# Sheet2.net
KiCad netlist of a schematic drawn in Altium Designer
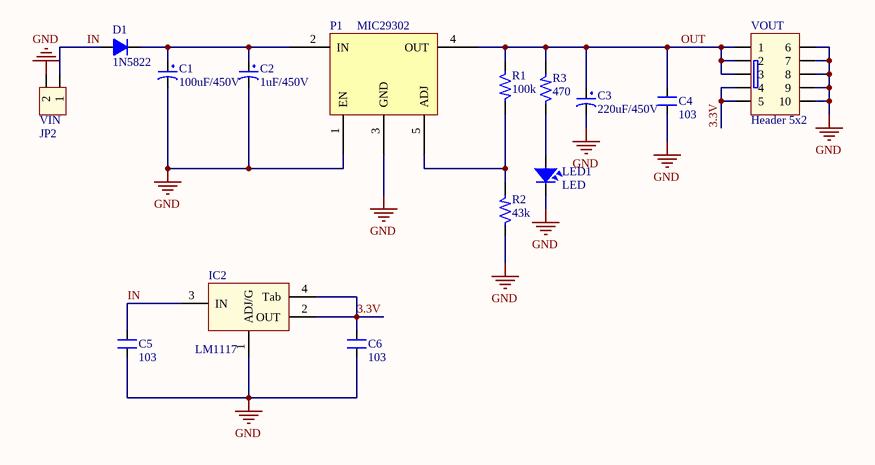
[diagram p0: Sheet2.SchDoc]

(export (version "E")
  (design (tool "Eeschema 10.0.6"))
  (components
    (comp (ref "C1")
      (value "100uF/450V")
      (footprint "CAP-D8-220uF/16V")
      (description "Cap 10000uF/63V")
      (libsource (lib "syhaunguyen") (part "CP9"))
    )
    (comp (ref "C2")
      (value "1uF/450V")
      (footprint "CAP0805")
      (description "Cap 10000uF/63V")
      (libsource (lib "syhaunguyen") (part "CP9"))
    )
    (comp (ref "C3")
      (value "220uF/450V")
      (footprint "CAP-D8-220uF/16V")
      (description "Cap 10000uF/63V")
      (libsource (lib "syhaunguyen") (part "CP9"))
    )
    (comp (ref "C4")
      (value "103")
      (footprint "SM-0805")
      (description "Cap SMD")
      (libsource (lib "syhaunguyen") (part "CM"))
    )
    (comp (ref "C5")
      (value "103")
      (footprint "SM-0805")
      (description "Cap SMD")
      (libsource (lib "syhaunguyen") (part "CM"))
    )
    (comp (ref "C6")
      (value "103")
      (footprint "SM-0805")
      (description "Cap SMD")
      (libsource (lib "syhaunguyen") (part "CM"))
    )
    (comp (ref "D1")
      (value "1N5822")
      (footprint "Diode1206")
      (description "Diode 5A")
      (libsource (lib "syhaunguyen") (part "D5A"))
    )
    (comp (ref "IC2")
      (value "LM1117")
      (footprint "SOT223-4N")
      (description "3v3")
      (libsource (lib "syhaunguyen") (part "LM1117"))
    )
    (comp (ref "LED1")
      (value "LED")
      (footprint "LED-5-RED")
      (description "LED Single colour Green and Red")
      (libsource (lib "syhaunguyen") (part "LED"))
    )
    (comp (ref "P1")
      (value "MIC29302")
      (footprint "LM2576_TO-263")
      (libsource (lib "Schlib1") (part "LM2576"))
    )
    (comp (ref "R1")
      (value "100k")
      (footprint "RES0805")
      (description "Resistor 1/4W")
      (libsource (lib "syhaunguyen") (part "R"))
    )
    (comp (ref "R2")
      (value "43k")
      (footprint "RES0805")
      (description "Resistor 1/4W")
      (libsource (lib "syhaunguyen") (part "R"))
    )
    (comp (ref "R3")
      (value "470")
      (footprint "RES0805")
      (description "Resistor 1/4W")
      (libsource (lib "syhaunguyen") (part "R"))
    )
    (comp (ref "VIN")
      (value "JP2")
      (footprint "DC-IN")
      (description "Connector 2")
      (libsource (lib "syhaunguyen") (part "Con2"))
    )
    (comp (ref "VOUT")
      (value "Header 5x2")
      (footprint "HED2X5_cen")
      (libsource (lib "syhaunguyen") (part "HED5x2"))
    )
  )
  (nets
    (net (code "1") (name "/3.3V") (class "Default")
      (node (ref "C6") (pin "2") (pinfunction "2_2") (pintype "passive"))
      (node (ref "IC2") (pin "2") (pinfunction "OUT_2") (pintype "passive"))
      (node (ref "IC2") (pin "4") (pinfunction "Tab_4") (pintype "passive"))
      (node (ref "VOUT") (pin "4") (pinfunction "4_4") (pintype "passive"))
      (node (ref "VOUT") (pin "5") (pinfunction "5_5") (pintype "passive"))
    )
    (net (code "2") (name "/IN") (class "Default")
      (node (ref "C5") (pin "2") (pinfunction "2_2") (pintype "passive"))
      (node (ref "D1") (pin "1") (pinfunction "A_1") (pintype "passive"))
      (node (ref "IC2") (pin "3") (pinfunction "IN_3") (pintype "passive"))
      (node (ref "VIN") (pin "1") (pinfunction "1_1") (pintype "passive"))
    )
    (net (code "3") (name "/OUT") (class "Default")
      (node (ref "C3") (pin "1") (pinfunction "1_1") (pintype "passive"))
      (node (ref "C4") (pin "2") (pinfunction "2_2") (pintype "passive"))
      (node (ref "P1") (pin "4") (pinfunction "OUT_4") (pintype "passive"))
      (node (ref "R1") (pin "1") (pinfunction "1_1") (pintype "passive"))
      (node (ref "R3") (pin "2") (pinfunction "2_2") (pintype "passive"))
      (node (ref "VOUT") (pin "1") (pinfunction "1_1") (pintype "passive"))
      (node (ref "VOUT") (pin "2") (pinfunction "2_2") (pintype "passive"))
      (node (ref "VOUT") (pin "3") (pinfunction "3_3") (pintype "passive"))
    )
    (net (code "4") (name "GND") (class "Default")
      (node (ref "C1") (pin "2") (pinfunction "2_2") (pintype "passive"))
      (node (ref "C2") (pin "2") (pinfunction "2_2") (pintype "passive"))
      (node (ref "C3") (pin "2") (pinfunction "2_2") (pintype "passive"))
      (node (ref "C4") (pin "1") (pinfunction "1_1") (pintype "passive"))
      (node (ref "C5") (pin "1") (pinfunction "1_1") (pintype "passive"))
      (node (ref "C6") (pin "1") (pinfunction "1_1") (pintype "passive"))
      (node (ref "IC2") (pin "1") (pinfunction "ADJ/G_1") (pintype "passive"))
      (node (ref "LED1") (pin "2") (pinfunction "2_2") (pintype "passive"))
      (node (ref "P1") (pin "1") (pinfunction "EN_1") (pintype "passive"))
      (node (ref "P1") (pin "3") (pinfunction "GND_3") (pintype "passive"))
      (node (ref "R2") (pin "1") (pinfunction "1_1") (pintype "passive"))
      (node (ref "VIN") (pin "2") (pinfunction "2_2") (pintype "passive"))
      (node (ref "VOUT") (pin "10") (pinfunction "10_10") (pintype "passive"))
      (node (ref "VOUT") (pin "6") (pinfunction "6_6") (pintype "passive"))
      (node (ref "VOUT") (pin "7") (pinfunction "7_7") (pintype "passive"))
      (node (ref "VOUT") (pin "8") (pinfunction "8_8") (pintype "passive"))
      (node (ref "VOUT") (pin "9") (pinfunction "9_9") (pintype "passive"))
    )
    (net (code "5") (name "Net-(D1-K)") (class "Default")
      (node (ref "C1") (pin "1") (pinfunction "1_1") (pintype "passive"))
      (node (ref "C2") (pin "1") (pinfunction "1_1") (pintype "passive"))
      (node (ref "D1") (pin "2") (pinfunction "K_2") (pintype "passive"))
      (node (ref "P1") (pin "2") (pinfunction "IN_2") (pintype "passive"))
    )
    (net (code "6") (name "Net-(LED1-Pad1)") (class "Default")
      (node (ref "LED1") (pin "1") (pinfunction "1_1") (pintype "passive"))
      (node (ref "R3") (pin "1") (pinfunction "1_1") (pintype "passive"))
    )
    (net (code "7") (name "Net-(P1-ADJ)") (class "Default")
      (node (ref "P1") (pin "5") (pinfunction "ADJ_5") (pintype "passive"))
      (node (ref "R1") (pin "2") (pinfunction "2_2") (pintype "passive"))
      (node (ref "R2") (pin "2") (pinfunction "2_2") (pintype "passive"))
    )
  )
)
